# SolarPanelCharger.net
KiCad netlist of a schematic drawn in Altium Designer
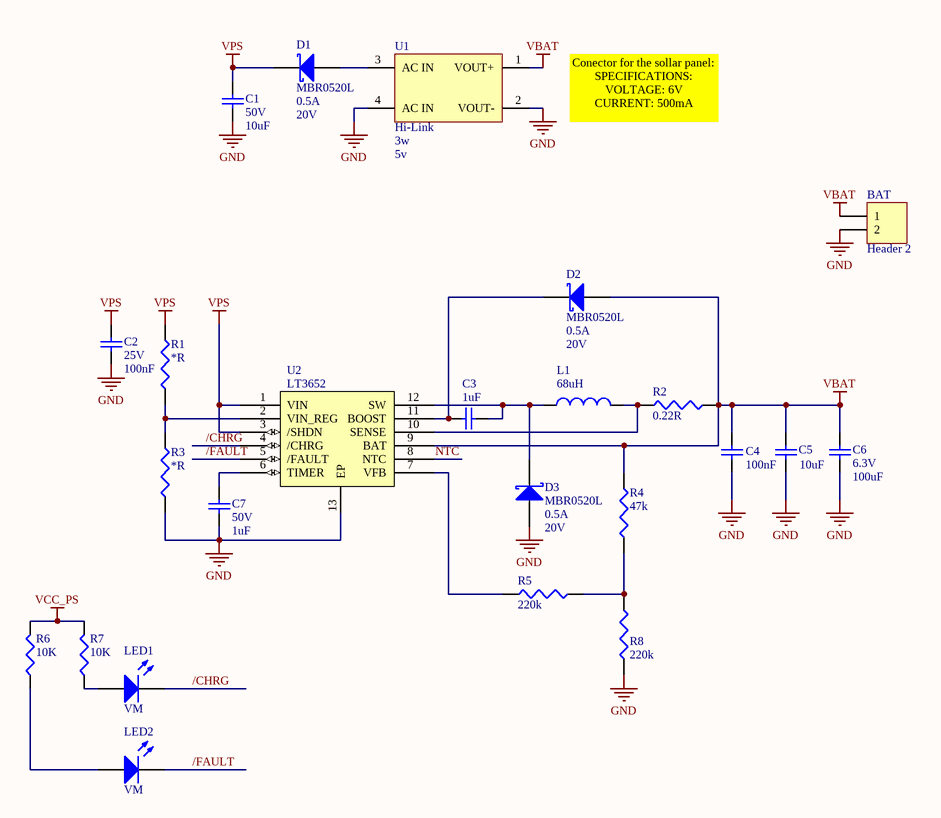
[diagram p0: SolarPanelCharger.SchDoc]

(export (version "E")
  (design (tool "Eeschema 10.0.6"))
  (components
    (comp (ref "BAT")
      (value "Header 2")
      (footprint "CONN XH2.54 - 2")
      (description "Header, 2-Pin")
      (libsource (lib "NavarroCON") (part "Header 2"))
    )
    (comp (ref "C1")
      (value "10uF")
      (footprint "CC1206")
      (description "Capacitor (Semiconductor SIM Model)")
      (fields (field (name "TENSÃO") "50V") (field (name "Comment") "Capacitor Cerâmico"))
      (libsource (lib "NavarroCAP") (part "Cap 10uF 50V 1206 X5R"))
    )
    (comp (ref "C2")
      (value "100nF")
      (footprint "CC0603")
      (description "Capacitor (Semiconductor SIM Model)")
      (fields (field (name "TENSÃO") "25V") (field (name "Comment") "Capacitor Cerâmico"))
      (libsource (lib "NavarroCAP") (part "Cap 100nF 25V 0603 X7R"))
    )
    (comp (ref "C3")
      (value "1uF")
      (footprint "CC0603")
      (description "Capacitor (Semiconductor SIM Model)")
      (fields (field (name "Comment") "Capacitor Cerâmico"))
      (libsource (lib "NavarroCAP") (part "Cap 1uF 50V 0603 X5R"))
    )
    (comp (ref "C4")
      (value "100nF")
      (footprint "CC0603")
      (description "Capacitor (Semiconductor SIM Model)")
      (fields (field (name "Comment") "Capacitor Cerâmico"))
      (libsource (lib "NavarroCAP") (part "Cap 100nF 25V 0603 X7R"))
    )
    (comp (ref "C5")
      (value "10uF")
      (footprint "CC0805")
      (description "Capacitor (Semiconductor SIM Model)")
      (fields (field (name "Comment") "Capacitor Cerâmico"))
      (libsource (lib "NavarroCAP") (part "Cap 10uF 50V 1206 X5R"))
    )
    (comp (ref "C6")
      (value "100uF")
      (footprint "CC1206")
      (description "Capacitor (Semiconductor SIM Model)")
      (fields (field (name "TENSÃO") "6.3V") (field (name "Comment") "Capacitor Cerâmico"))
      (libsource (lib "NavarroCAP") (part "Cap 100uF 6.3V 1206 X5R"))
    )
    (comp (ref "C7")
      (value "1uF")
      (footprint "CC0603")
      (description "Capacitor (Semiconductor SIM Model)")
      (fields (field (name "TENSÃO") "50V") (field (name "Comment") "Capacitor Cerâmico"))
      (libsource (lib "NavarroCAP") (part "Cap 1uF 50V 0603 X5R"))
    )
    (comp (ref "D1")
      (value "MBR0520L")
      (footprint "SOD-123F")
      (description "Schottky Diode")
      (fields (field (name "CORRENTE") "0.5A") (field (name "TENSÃO") "20V"))
      (libsource (lib "NavarroSEMI") (part "DS 20V 0.5A 385mV SOD-123"))
    )
    (comp (ref "D2")
      (value "MBR0520L")
      (footprint "SOD-123F")
      (description "Schottky Diode")
      (fields (field (name "CORRENTE") "0.5A") (field (name "TENSÃO") "20V"))
      (libsource (lib "NavarroSEMI") (part "DS 20V 0.5A 385mV SOD-123"))
    )
    (comp (ref "D3")
      (value "MBR0520L")
      (footprint "SOD-123F")
      (description "Schottky Diode")
      (fields (field (name "CORRENTE") "0.5A") (field (name "TENSÃO") "20V"))
      (libsource (lib "NavarroSEMI") (part "DS 20V 0.5A 385mV SOD-123"))
    )
    (comp (ref "L1")
      (value "68uH")
      (footprint "MURATA 4600")
      (description "Inductor")
      (fields (field (name "Comment") "Indutor"))
      (libsource (lib "NavarroIND") (part "Ind 68uH 1.05A"))
    )
    (comp (ref "LED1")
      (value "VM")
      (footprint "LED 0603")
      (description "LED")
      (libsource (lib "NavarroSEMI") (part "LED"))
    )
    (comp (ref "LED2")
      (value "VM")
      (footprint "LED 0603")
      (description "LED")
      (libsource (lib "NavarroSEMI") (part "LED"))
    )
    (comp (ref "R1")
      (value "*R")
      (footprint "CC0603")
      (description "Resistor")
      (libsource (lib "NavarroRES") (part "Res - $Val $% $Footprint $Pot"))
    )
    (comp (ref "R2")
      (value "0.22R")
      (footprint "CC1206")
      (description "Resistor")
      (libsource (lib "NavarroRES") (part "Res 0.22R 1% 1206 1/4W"))
    )
    (comp (ref "R3")
      (value "*R")
      (footprint "CC0603")
      (description "Resistor")
      (libsource (lib "NavarroRES") (part "Res - $Val $% $Footprint $Pot"))
    )
    (comp (ref "R4")
      (value "47k")
      (footprint "CC0603")
      (description "Resistor")
      (libsource (lib "NavarroRES") (part "Res - $Val $% $Footprint $Pot"))
    )
    (comp (ref "R5")
      (value "220k")
      (footprint "CC0603")
      (description "Resistor")
      (libsource (lib "NavarroRES") (part "Res - $Val $% $Footprint $Pot"))
    )
    (comp (ref "R6")
      (value "10K")
      (footprint "CC0603")
      (description "Resistor")
      (libsource (lib "NavarroRES") (part "Res 10K 1% 0603 1/10W"))
    )
    (comp (ref "R7")
      (value "10K")
      (footprint "CC0603")
      (description "Resistor")
      (libsource (lib "NavarroRES") (part "Res 10K 1% 0603 1/10W"))
    )
    (comp (ref "R8")
      (value "220k")
      (footprint "CC0603")
      (description "Resistor")
      (libsource (lib "NavarroRES") (part "Res - $Val $% $Footprint $Pot"))
    )
    (comp (ref "U1")
      (value "Hi-Link")
      (footprint "Fonte-HILINK")
      (description "Fonte chaveada isolada")
      (fields (field (name "POTÊNCIA") "3w") (field (name "TENSÃO") "5v"))
      (libsource (lib "Navarro") (part "Fonte Hi-Link"))
    )
    (comp (ref "U2")
      (value "LT3652")
      (footprint "MSOP-12N_EP")
      (description "Power Tracking 2A Battery  Charger for Solar Power")
      (libsource (lib "Navarro") (part "LT3652"))
    )
  )
  (nets
    (net (code "1") (name "/NTC") (class "Default")
      (node (ref "U2") (pin "8") (pinfunction "NTC_8") (pintype "passive"))
    )
    (net (code "2") (name "/{slash}CHRG") (class "Default")
      (node (ref "LED1") (pin "2") (pinfunction "K_2") (pintype "passive"))
      (node (ref "U2") (pin "4") (pinfunction "/CHRG_4") (pintype "bidirectional"))
    )
    (net (code "3") (name "/{slash}FAULT") (class "Default")
      (node (ref "LED2") (pin "2") (pinfunction "K_2") (pintype "passive"))
      (node (ref "U2") (pin "5") (pinfunction "/FAULT_5") (pintype "bidirectional"))
    )
    (net (code "4") (name "GND") (class "Default")
      (node (ref "BAT") (pin "2") (pinfunction "2_2") (pintype "passive"))
      (node (ref "C1") (pin "1") (pinfunction "1_1") (pintype "passive"))
      (node (ref "C2") (pin "1") (pinfunction "1_1") (pintype "passive"))
      (node (ref "C4") (pin "1") (pinfunction "1_1") (pintype "passive"))
      (node (ref "C5") (pin "1") (pinfunction "1_1") (pintype "passive"))
      (node (ref "C6") (pin "1") (pinfunction "1_1") (pintype "passive"))
      (node (ref "C7") (pin "1") (pinfunction "1_1") (pintype "passive"))
      (node (ref "D3") (pin "1") (pinfunction "A_1") (pintype "passive"))
      (node (ref "R3") (pin "1") (pinfunction "1_1") (pintype "passive"))
      (node (ref "R8") (pin "1") (pinfunction "1_1") (pintype "passive"))
      (node (ref "U1") (pin "2") (pinfunction "VOUT-_2") (pintype "power_in"))
      (node (ref "U1") (pin "4") (pinfunction "AC_IN_4") (pintype "power_in"))
      (node (ref "U2") (pin "13") (pinfunction "EP_13") (pintype "passive"))
    )
    (net (code "5") (name "Net-(D1-A)") (class "Default")
      (node (ref "D1") (pin "1") (pinfunction "A_1") (pintype "passive"))
      (node (ref "U1") (pin "3") (pinfunction "AC_IN_3") (pintype "power_in"))
    )
    (net (code "6") (name "Net-(D2-K)") (class "Default")
      (node (ref "C3") (pin "1") (pinfunction "1_1") (pintype "passive"))
      (node (ref "D2") (pin "2") (pinfunction "K_2") (pintype "passive"))
      (node (ref "U2") (pin "11") (pinfunction "BOOST_11") (pintype "passive"))
    )
    (net (code "7") (name "Net-(D3-K)") (class "Default")
      (node (ref "C3") (pin "2") (pinfunction "2_2") (pintype "passive"))
      (node (ref "D3") (pin "2") (pinfunction "K_2") (pintype "passive"))
      (node (ref "L1") (pin "1") (pinfunction "1_1") (pintype "passive"))
      (node (ref "U2") (pin "12") (pinfunction "SW_12") (pintype "passive"))
    )
    (net (code "8") (name "Net-(LED1-A)") (class "Default")
      (node (ref "LED1") (pin "1") (pinfunction "A_1") (pintype "passive"))
      (node (ref "R7") (pin "1") (pinfunction "1_1") (pintype "passive"))
    )
    (net (code "9") (name "Net-(LED2-A)") (class "Default")
      (node (ref "LED2") (pin "1") (pinfunction "A_1") (pintype "passive"))
      (node (ref "R6") (pin "1") (pinfunction "1_1") (pintype "passive"))
    )
    (net (code "10") (name "Net-(R4-Pad1)") (class "Default")
      (node (ref "R4") (pin "1") (pinfunction "1_1") (pintype "passive"))
      (node (ref "R5") (pin "1") (pinfunction "1_1") (pintype "passive"))
      (node (ref "R8") (pin "2") (pinfunction "2_2") (pintype "passive"))
    )
    (net (code "11") (name "Net-(U2-SENSE)") (class "Default")
      (node (ref "L1") (pin "2") (pinfunction "2_2") (pintype "passive"))
      (node (ref "R2") (pin "1") (pinfunction "1_1") (pintype "passive"))
      (node (ref "U2") (pin "10") (pinfunction "SENSE_10") (pintype "passive"))
    )
    (net (code "12") (name "Net-(U2-TIMER)") (class "Default")
      (node (ref "C7") (pin "2") (pinfunction "2_2") (pintype "passive"))
      (node (ref "U2") (pin "6") (pinfunction "TIMER_6") (pintype "bidirectional"))
    )
    (net (code "13") (name "Net-(U2-VFB)") (class "Default")
      (node (ref "R5") (pin "2") (pinfunction "2_2") (pintype "passive"))
      (node (ref "U2") (pin "7") (pinfunction "VFB_7") (pintype "passive"))
    )
    (net (code "14") (name "Net-(U2-VIN_REG)") (class "Default")
      (node (ref "R1") (pin "1") (pinfunction "1_1") (pintype "passive"))
      (node (ref "R3") (pin "2") (pinfunction "2_2") (pintype "passive"))
      (node (ref "U2") (pin "2") (pinfunction "VIN_REG_2") (pintype "power_in"))
    )
    (net (code "15") (name "VBAT") (class "Default")
      (node (ref "BAT") (pin "1") (pinfunction "1_1") (pintype "passive"))
      (node (ref "C4") (pin "2") (pinfunction "2_2") (pintype "passive"))
      (node (ref "C5") (pin "2") (pinfunction "2_2") (pintype "passive"))
      (node (ref "C6") (pin "2") (pinfunction "2_2") (pintype "passive"))
      (node (ref "D2") (pin "1") (pinfunction "A_1") (pintype "passive"))
      (node (ref "R2") (pin "2") (pinfunction "2_2") (pintype "passive"))
      (node (ref "R4") (pin "2") (pinfunction "2_2") (pintype "passive"))
      (node (ref "U1") (pin "1") (pinfunction "VOUT+_1") (pintype "power_in"))
      (node (ref "U2") (pin "9") (pinfunction "BAT_9") (pintype "power_in"))
    )
    (net (code "16") (name "VCC_PS") (class "Default")
      (node (ref "R6") (pin "2") (pinfunction "2_2") (pintype "passive"))
      (node (ref "R7") (pin "2") (pinfunction "2_2") (pintype "passive"))
    )
    (net (code "17") (name "VPS") (class "Default")
      (node (ref "C1") (pin "2") (pinfunction "2_2") (pintype "passive"))
      (node (ref "C2") (pin "2") (pinfunction "2_2") (pintype "passive"))
      (node (ref "D1") (pin "2") (pinfunction "K_2") (pintype "passive"))
      (node (ref "R1") (pin "2") (pinfunction "2_2") (pintype "passive"))
      (node (ref "U2") (pin "1") (pinfunction "VIN_1") (pintype "power_in"))
      (node (ref "U2") (pin "3") (pinfunction "/SHDN_3") (pintype "bidirectional"))
    )
  )
)
